# Digital.net
KiCad netlist of a schematic drawn in Altium Designer
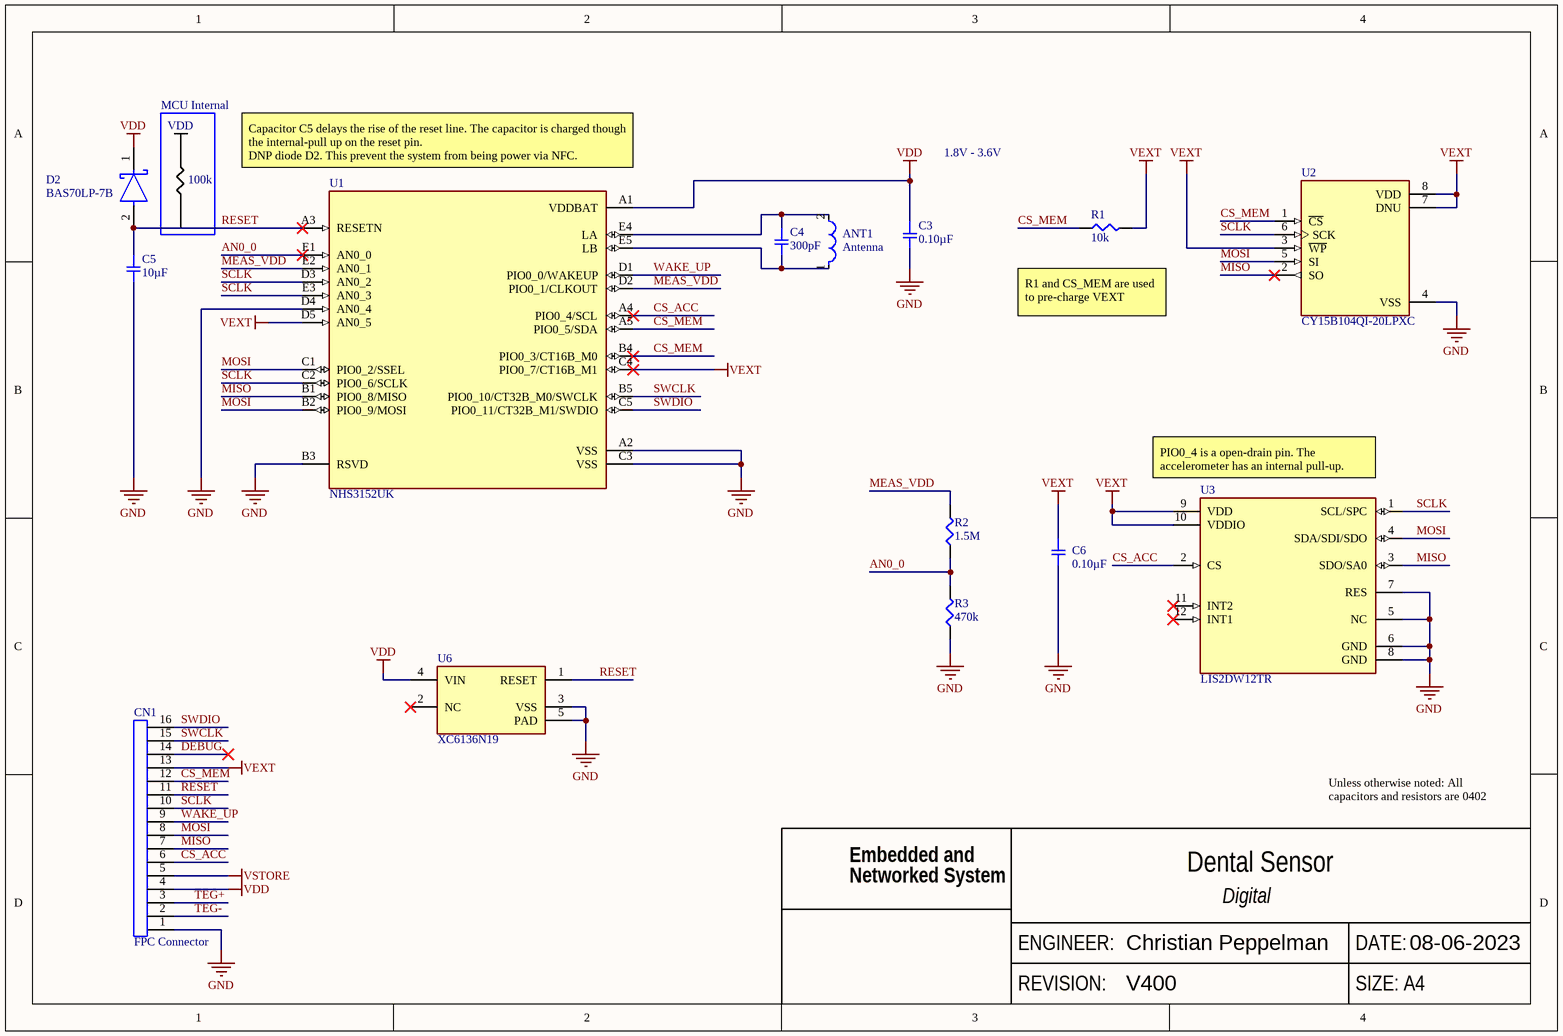
[diagram p0: Digital.SchDoc]

(export (version "E")
  (design (tool "Eeschema 10.0.6"))
  (components
    (comp (ref "ANT1")
      (value "Antenna")
      (footprint "NFC Antenna")
      (description "Track 0.2; Gap 0.1; Height 4.6; Width 14.5;")
      (libsource (lib "Library") (part "NFC Antenna"))
    )
    (comp (ref "C3")
      (value "0.10µF")
      (footprint "RESC1005X03N")
      (description "CAP CER 0.1UF 6.3V X5R 0402")
      (fields
        (field (name "DIGI-KEY PART NUMBER") "490-6287-1-ND")
        (field (name "PART NUMBER") "GRM155R60J104KA01D")
      )
      (libsource (lib "capacitor_murata_0402") (part "GRM155R60J104KA01D"))
    )
    (comp (ref "C4")
      (value "300pF")
      (footprint "RESC1005X03N")
      (description "CAP CER 300PF 50V NP0 0402")
      (fields
        (field (name "DIGI-KEY PART NUMBER") "490-3234-1-ND")
        (field (name "PART NUMBER") "GRM1555C1H301JA01D")
      )
      (libsource (lib "capacitor_murata_0402") (part "GRM1555C1H301JA01D"))
    )
    (comp (ref "C5")
      (value "10µF")
      (footprint "RESC1005X03N")
      (description "CAP CER 10UF 6.3V X5R 0402")
      (fields
        (field (name "DIGI-KEY PART NUMBER") "490-13211-1-ND")
        (field (name "PART NUMBER") "GRJ155R60J106ME11D")
      )
      (libsource (lib "capacitor_murata_0402") (part "GRJ155R60J106ME11D"))
    )
    (comp (ref "C6")
      (value "0.10µF")
      (footprint "RESC1005X03N")
      (description "CAP CER 0.1UF 6.3V X5R 0402")
      (fields
        (field (name "DIGI-KEY PART NUMBER") "490-6287-1-ND")
        (field (name "PART NUMBER") "GRM155R60J104KA01D")
      )
      (libsource (lib "capacitor_murata_0402") (part "GRM155R60J104KA01D"))
    )
    (comp (ref "CN1")
      (value "FPC Connector")
      (footprint "52745-1697")
      (description "FFC / FPC Board Connector, 0.5 mm, 16 Contacts, Receptacle, Easy-On 52745, Surface Mount, Top")
      (libsource (lib "Library") (part "52745-1697"))
    )
    (comp (ref "D2")
      (value "BAS70LP-7B")
      (footprint "FP-X1-DFN1006-2-MFG")
      (description "DIODE SCHTTKY 70V 70MA X1DFN1006")
      (fields
        (field (name "MANUFACTURER") "Diodes Inc.")
        (field (name "OCTOPART") "https://octopart.com/bas70lp-7b-diodes+inc.-22053921")
      )
      (libsource (lib "Altium Content Vault") (part "1d6ec82d83fb6aee721767c19dac4b9"))
    )
    (comp (ref "R1")
      (value "10k")
      (footprint "RESC1005X03N")
      (description "RES SMD 10K OHM 5% 1/10W 0402")
      (fields (field (name "PART NUMBER") "ERJ-2GEJ103X") (field (name "DIGI-KEY PART NUMBER") "P10KJCT-ND"))
      (libsource (lib "Panasonic_ERJ_0402") (part "ERJ-2GEJ103X"))
    )
    (comp (ref "R2")
      (value "1.5M")
      (footprint "RESC1005X03N")
      (description "RES SMD 1.5M OHM 5% 1/10W 0402")
      (fields (field (name "PART NUMBER") "ERJ-2GEJ155X") (field (name "DIGI-KEY PART NUMBER") "P1.5MJCT-ND"))
      (libsource (lib "Panasonic_ERJ_0402") (part "ERJ-2GEJ155X"))
    )
    (comp (ref "R3")
      (value "470k")
      (footprint "RESC1005X03N")
      (description "RES SMD 470K OHM 1% 1/10W 0402")
      (fields
        (field (name "PART NUMBER") "ERJ-2RKF4703X")
        (field (name "DIGI-KEY PART NUMBER") "P470KLCT-ND")
      )
      (libsource (lib "Panasonic_ERJ_0402") (part "ERJ-2RKF4703X"))
    )
    (comp (ref "U1")
      (value "NHS3152UK")
      (footprint "WLCSP25")
      (description "ARM-microcontrollers - MCU NTAG NHS3152 NFC")
      (libsource (lib "Library") (part "NHS3152UK"))
    )
    (comp (ref "U2")
      (value "CY15B104QI-20LPXC")
      (footprint "8-GQFN")
      (description "FRAM (Ferroelectric RAM) Memory IC 4Mbit SPI 20 MHz 8-GQFN (3.23x3.28)")
      (libsource (lib "Library") (part "CY15B104QI-20LPXC"))
    )
    (comp (ref "U3")
      (value "LIS2DW12TR")
      (footprint "FP-LGA12-DM00170568-MFG")
      (description "ACCEL 2-16G I2C/SPI 12LGA")
      (fields
        (field (name "OCTOPART") "https://octopart.com/lis2dw12tr-stmicroelectronics-77080925")
        (field (name "MANUFACTURER") "STMicroelectronics")
      )
      (libsource (lib "Altium Content Vault") (part "8197bdef8f004bf043f7592a5d62978"))
    )
    (comp (ref "U6")
      (value "XC6136N19")
      (footprint "USPQ-4B05")
      (description "Controlecircuits Ultra-Low Power (88nA) Voltage Detector")
      (libsource (lib "Library") (part "XC6136C19ANR-G"))
    )
  )
  (nets
    (net (code "1") (name "/AN0_0") (class "Default")
      (node (ref "R2") (pin "1") (pinfunction "1_1") (pintype "passive"))
      (node (ref "R3") (pin "2") (pinfunction "2_2") (pintype "passive"))
      (node (ref "U1") (pin "E1") (pinfunction "AN0_0_E1") (pintype "input"))
    )
    (net (code "2") (name "/CS_ACC") (class "Default")
      (node (ref "CN1") (pin "6") (pintype "passive"))
      (node (ref "U1") (pin "A4") (pinfunction "PIO0_4/SCL_A4") (pintype "bidirectional"))
      (node (ref "U3") (pin "2") (pinfunction "CS_2") (pintype "input"))
    )
    (net (code "3") (name "/CS_MEM") (class "Default")
      (node (ref "CN1") (pin "12") (pintype "passive"))
      (node (ref "R1") (pin "1") (pinfunction "1_1") (pintype "passive"))
      (node (ref "U1") (pin "A5") (pinfunction "PIO0_5/SDA_A5") (pintype "bidirectional"))
      (node (ref "U1") (pin "B4") (pinfunction "PIO0_3/CT16B_M0_B4") (pintype "bidirectional"))
      (node (ref "U2") (pin "1") (pinfunction "~{CS}_1") (pintype "input"))
    )
    (net (code "4") (name "/DEBUG") (class "Default")
      (node (ref "CN1") (pin "14") (pintype "passive+no_connect"))
    )
    (net (code "5") (name "/MEAS_VDD") (class "Default")
      (node (ref "R2") (pin "2") (pinfunction "2_2") (pintype "passive"))
      (node (ref "U1") (pin "D2") (pinfunction "PIO0_1/CLKOUT_D2") (pintype "bidirectional"))
      (node (ref "U1") (pin "E2") (pinfunction "AN0_1_E2") (pintype "input"))
    )
    (net (code "6") (name "/MISO") (class "Default")
      (node (ref "CN1") (pin "7") (pintype "passive"))
      (node (ref "U1") (pin "B1") (pinfunction "PIO0_8/MISO_B1") (pintype "bidirectional"))
      (node (ref "U2") (pin "2") (pinfunction "SO_2") (pintype "output"))
      (node (ref "U3") (pin "3") (pinfunction "SDO/SA0_3") (pintype "bidirectional"))
    )
    (net (code "7") (name "/MOSI") (class "Default")
      (node (ref "CN1") (pin "8") (pintype "passive"))
      (node (ref "U1") (pin "B2") (pinfunction "PIO0_9/MOSI_B2") (pintype "bidirectional"))
      (node (ref "U1") (pin "C1") (pinfunction "PIO0_2/SSEL_C1") (pintype "bidirectional"))
      (node (ref "U2") (pin "5") (pinfunction "SI_5") (pintype "input"))
      (node (ref "U3") (pin "4") (pinfunction "SDA/SDI/SDO_4") (pintype "bidirectional"))
    )
    (net (code "8") (name "/RESET") (class "Default")
      (node (ref "C5") (pin "1") (pinfunction "1_1") (pintype "passive"))
      (node (ref "CN1") (pin "11") (pintype "passive"))
      (node (ref "D2") (pin "2") (pinfunction "A_2") (pintype "passive"))
      (node (ref "U1") (pin "A3") (pinfunction "RESETN_A3") (pintype "input"))
      (node (ref "U6") (pin "1") (pinfunction "RESET_1") (pintype "power_in"))
    )
    (net (code "9") (name "/SCLK") (class "Default")
      (node (ref "CN1") (pin "10") (pintype "passive"))
      (node (ref "U1") (pin "C2") (pinfunction "PIO0_6/SCLK_C2") (pintype "bidirectional"))
      (node (ref "U1") (pin "D3") (pinfunction "AN0_2_D3") (pintype "input"))
      (node (ref "U1") (pin "E3") (pinfunction "AN0_3_E3") (pintype "input"))
      (node (ref "U2") (pin "6") (pinfunction "SCK_6") (pintype "input"))
      (node (ref "U3") (pin "1") (pinfunction "SCL/SPC_1") (pintype "bidirectional"))
    )
    (net (code "10") (name "/SWCLK") (class "Default")
      (node (ref "CN1") (pin "15") (pintype "passive"))
      (node (ref "U1") (pin "B5") (pinfunction "PIO0_10/CT32B_M0/SWCLK_B5") (pintype "bidirectional"))
    )
    (net (code "11") (name "/SWDIO") (class "Default")
      (node (ref "CN1") (pin "16") (pintype "passive"))
      (node (ref "U1") (pin "C5") (pinfunction "PIO0_11/CT32B_M1/SWDIO_C5") (pintype "bidirectional"))
    )
    (net (code "12") (name "/TEG+") (class "Default") (node (ref "CN1") (pin "3") (pintype "passive")))
    (net (code "13") (name "/TEG-") (class "Default") (node (ref "CN1") (pin "2") (pintype "passive")))
    (net (code "14") (name "/WAKE_UP") (class "Default")
      (node (ref "CN1") (pin "9") (pintype "passive"))
      (node (ref "U1") (pin "D1") (pinfunction "PIO0_0/WAKEUP_D1") (pintype "bidirectional"))
    )
    (net (code "15") (name "GND") (class "Default")
      (node (ref "C3") (pin "2") (pinfunction "2_2") (pintype "passive"))
      (node (ref "C5") (pin "2") (pinfunction "2_2") (pintype "passive"))
      (node (ref "C6") (pin "2") (pinfunction "2_2") (pintype "passive"))
      (node (ref "CN1") (pin "1") (pintype "passive"))
      (node (ref "R3") (pin "1") (pinfunction "1_1") (pintype "passive"))
      (node (ref "U1") (pin "A2") (pinfunction "VSS_A2") (pintype "power_in"))
      (node (ref "U1") (pin "B3") (pinfunction "RSVD_B3") (pintype "passive"))
      (node (ref "U1") (pin "C3") (pinfunction "VSS_C3") (pintype "power_in"))
      (node (ref "U1") (pin "D4") (pinfunction "AN0_4_D4") (pintype "input"))
      (node (ref "U2") (pin "4") (pinfunction "VSS_4") (pintype "power_in"))
      (node (ref "U3") (pin "5") (pinfunction "NC_5") (pintype "passive"))
      (node (ref "U3") (pin "6") (pinfunction "GND_6") (pintype "power_in"))
      (node (ref "U3") (pin "7") (pinfunction "RES_7") (pintype "passive"))
      (node (ref "U3") (pin "8") (pinfunction "GND_8") (pintype "power_in"))
      (node (ref "U6") (pin "3") (pinfunction "VSS_3") (pintype "power_in"))
      (node (ref "U6") (pin "5") (pinfunction "PAD_5") (pintype "power_in"))
    )
    (net (code "16") (name "Net-(U1-LA)") (class "Default")
      (node (ref "ANT1") (pin "2") (pinfunction "2_2") (pintype "passive"))
      (node (ref "C4") (pin "1") (pinfunction "1_1") (pintype "passive"))
      (node (ref "U1") (pin "E4") (pinfunction "LA_E4") (pintype "bidirectional"))
    )
    (net (code "17") (name "Net-(U1-LB)") (class "Default")
      (node (ref "ANT1") (pin "1") (pinfunction "1_1") (pintype "passive"))
      (node (ref "C4") (pin "2") (pinfunction "2_2") (pintype "passive"))
      (node (ref "U1") (pin "E5") (pinfunction "LB_E5") (pintype "bidirectional"))
    )
    (net (code "18") (name "VDD") (class "Default")
      (node (ref "C3") (pin "1") (pinfunction "1_1") (pintype "passive"))
      (node (ref "CN1") (pin "4") (pintype "passive"))
      (node (ref "D2") (pin "1") (pinfunction "C_1") (pintype "passive"))
      (node (ref "U1") (pin "A1") (pinfunction "VDDBAT_A1") (pintype "power_in"))
      (node (ref "U6") (pin "4") (pinfunction "VIN_4") (pintype "power_in"))
    )
    (net (code "19") (name "VEXT") (class "Default")
      (node (ref "C6") (pin "1") (pinfunction "1_1") (pintype "passive"))
      (node (ref "CN1") (pin "13") (pintype "passive"))
      (node (ref "R1") (pin "2") (pinfunction "2_2") (pintype "passive"))
      (node (ref "U1") (pin "C4") (pinfunction "PIO0_7/CT16B_M1_C4") (pintype "bidirectional"))
      (node (ref "U1") (pin "D5") (pinfunction "AN0_5_D5") (pintype "input"))
      (node (ref "U2") (pin "3") (pinfunction "~{WP}_3") (pintype "input"))
      (node (ref "U2") (pin "7") (pinfunction "DNU_7") (pintype "passive"))
      (node (ref "U2") (pin "8") (pinfunction "VDD_8") (pintype "power_in"))
      (node (ref "U3") (pin "10") (pinfunction "VDDIO_10") (pintype "power_in"))
      (node (ref "U3") (pin "9") (pinfunction "VDD_9") (pintype "power_in"))
    )
    (net (code "20") (name "VSTORE") (class "Default") (node (ref "CN1") (pin "5") (pintype "passive")))
    (net (code "21") (name "unconnected-(U3-INT1-Pad12)") (class "Default")
      (node (ref "U3") (pin "12") (pinfunction "INT1_12") (pintype "input+no_connect"))
    )
    (net (code "22") (name "unconnected-(U3-INT2-Pad11)") (class "Default")
      (node (ref "U3") (pin "11") (pinfunction "INT2_11") (pintype "input+no_connect"))
    )
    (net (code "23") (name "unconnected-(U6-NC-Pad2)") (class "Default")
      (node (ref "U6") (pin "2") (pinfunction "NC_2") (pintype "power_in+no_connect"))
    )
  )
)
